# BPF_LNA_1550A.net
KiCad netlist of a schematic drawn in EAGLE
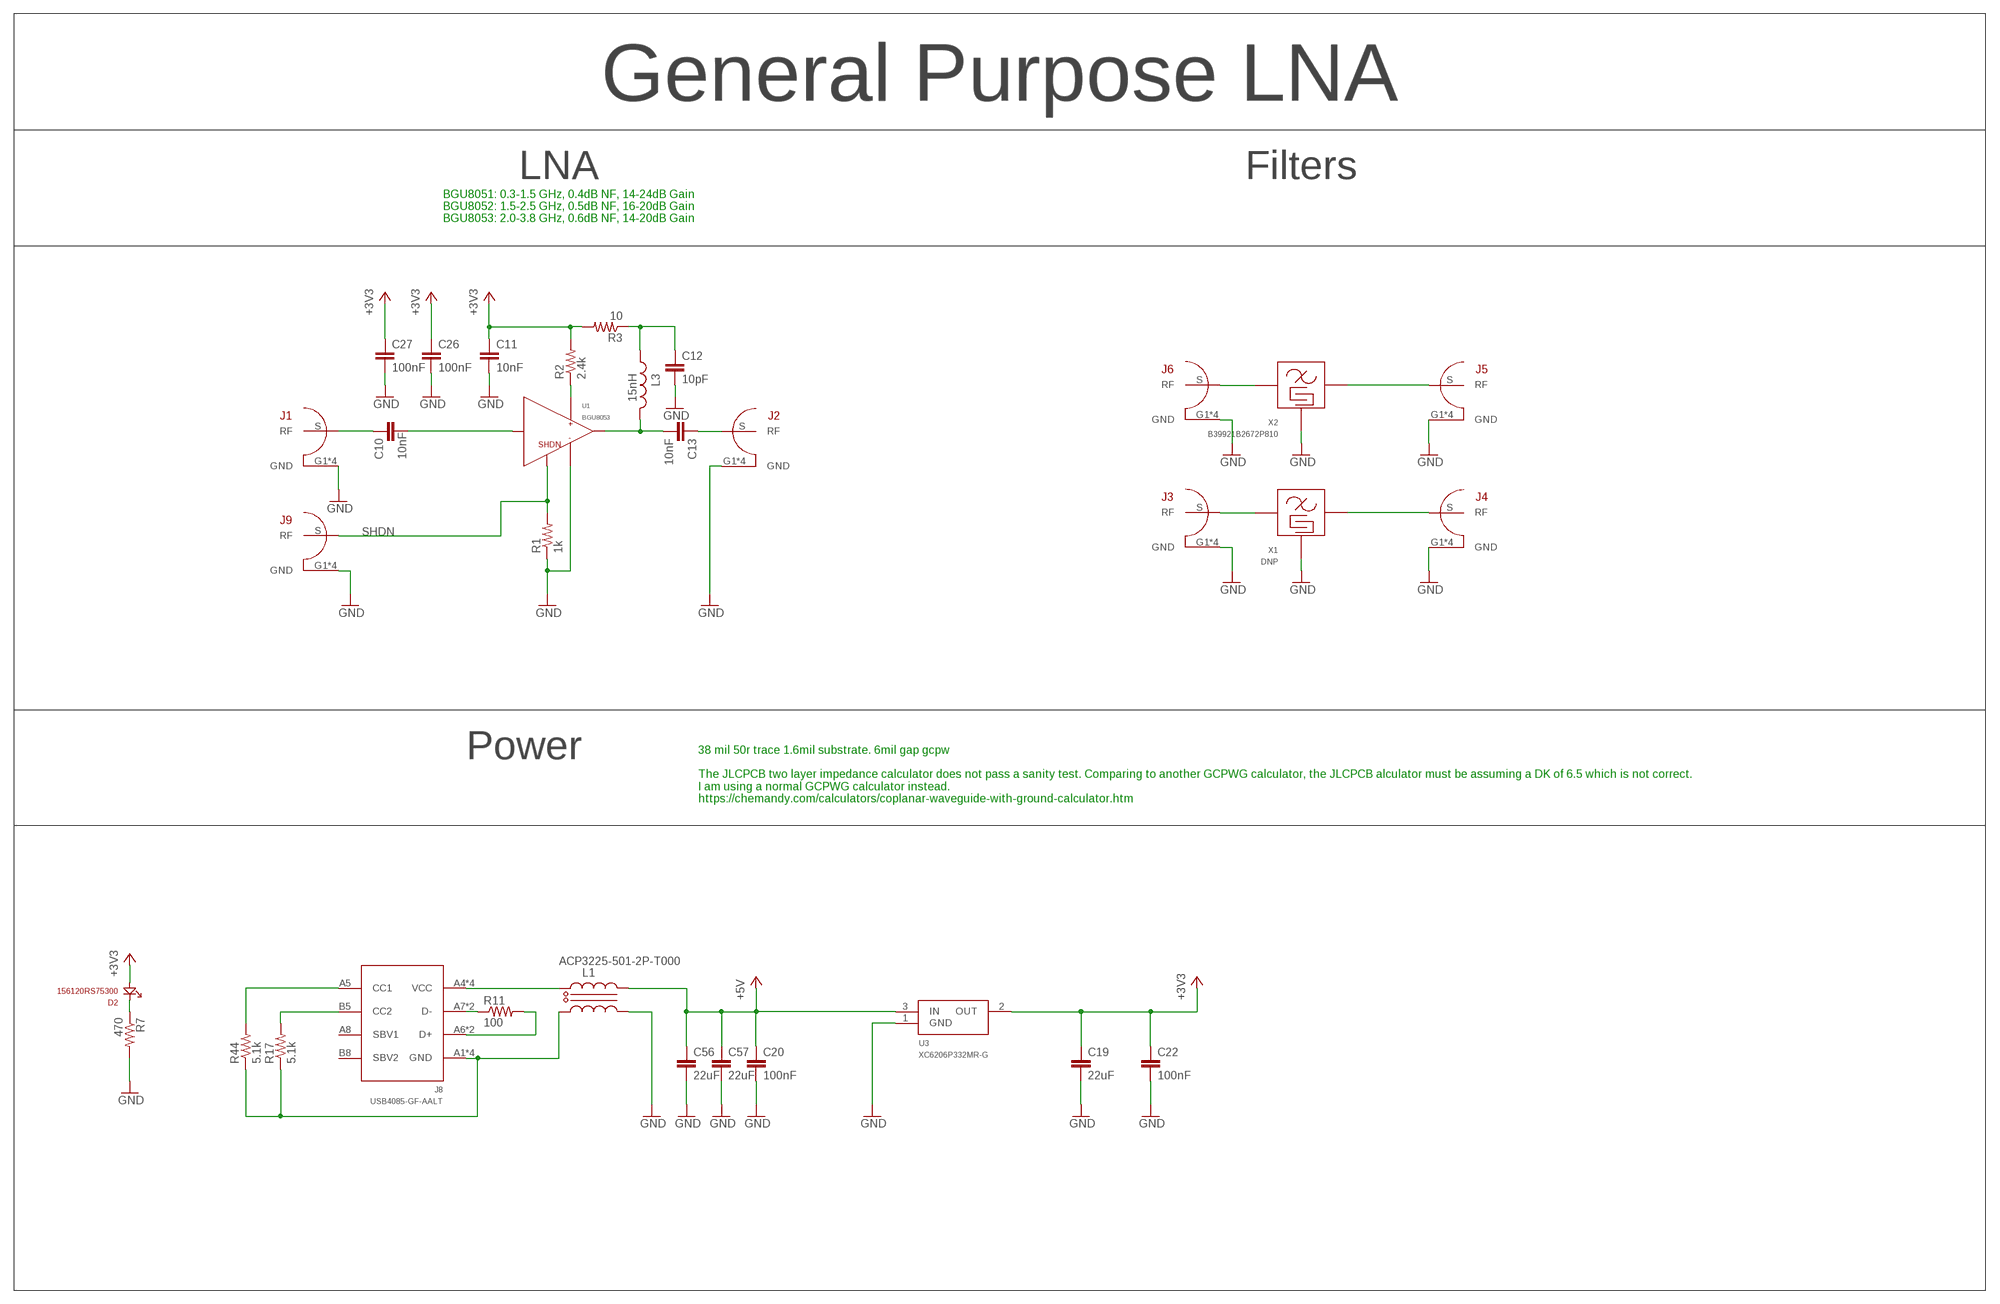
[diagram p0: schematic, sheet 1]

(export (version "E")
  (design (tool "Eeschema 10.0.6"))
  (components
    (comp (ref "C10")
      (value "10nF")
      (footprint "eagle-import:0603")
      (libsource (lib "eagle-import") (part "0603_CAPACITOR"))
    )
    (comp (ref "C11")
      (value "10nF")
      (footprint "eagle-import:0603")
      (libsource (lib "eagle-import") (part "0603_CAPACITOR"))
    )
    (comp (ref "C12")
      (value "10pF")
      (footprint "eagle-import:0603")
      (libsource (lib "eagle-import") (part "0603_CAPACITOR"))
    )
    (comp (ref "C13")
      (value "10nF")
      (footprint "eagle-import:0603")
      (libsource (lib "eagle-import") (part "0603_CAPACITOR"))
    )
    (comp (ref "C19")
      (value "22uF")
      (footprint "eagle-import:C1206")
      (libsource (lib "eagle-import") (part "C-EUC1206"))
    )
    (comp (ref "C20")
      (value "100nF")
      (footprint "eagle-import:0603")
      (libsource (lib "eagle-import") (part "0603_CAPACITOR"))
    )
    (comp (ref "C22")
      (value "100nF")
      (footprint "eagle-import:0603")
      (libsource (lib "eagle-import") (part "0603_CAPACITOR"))
    )
    (comp (ref "C26")
      (value "100nF")
      (footprint "eagle-import:0603")
      (libsource (lib "eagle-import") (part "0603_CAPACITOR"))
    )
    (comp (ref "C27")
      (value "100nF")
      (footprint "eagle-import:0603")
      (libsource (lib "eagle-import") (part "0603_CAPACITOR"))
    )
    (comp (ref "C56")
      (value "22uF")
      (footprint "eagle-import:C1206")
      (libsource (lib "eagle-import") (part "C-EUC1206"))
    )
    (comp (ref "C57")
      (value "22uF")
      (footprint "eagle-import:C1206")
      (libsource (lib "eagle-import") (part "C-EUC1206"))
    )
    (comp (ref "D2")
      (value "156120RS75300")
      (footprint "eagle-import:1206_REV")
      (fields (field (name "PARTNO") "732-5031-1-ND"))
      (libsource (lib "eagle-import") (part "156120RS75300"))
    )
    (comp (ref "J1")
      (value "0733910070")
      (footprint "eagle-import:CONREVSMA008-G")
      (fields (field (name "PARTNO") "WM5544-ND"))
      (libsource (lib "eagle-import") (part "0733910070"))
    )
    (comp (ref "J2")
      (value "0733910070")
      (footprint "eagle-import:CONREVSMA008-G")
      (fields (field (name "PARTNO") "WM5544-ND"))
      (libsource (lib "eagle-import") (part "0733910070"))
    )
    (comp (ref "J3")
      (value "0733910070")
      (footprint "eagle-import:CONREVSMA008-G")
      (fields (field (name "PARTNO") "WM5544-ND"))
      (libsource (lib "eagle-import") (part "0733910070"))
    )
    (comp (ref "J4")
      (value "0733910070")
      (footprint "eagle-import:CONREVSMA008-G")
      (fields (field (name "PARTNO") "WM5544-ND"))
      (libsource (lib "eagle-import") (part "0733910070"))
    )
    (comp (ref "J5")
      (value "0733910070")
      (footprint "eagle-import:CONREVSMA008-G")
      (fields (field (name "PARTNO") "WM5544-ND"))
      (libsource (lib "eagle-import") (part "0733910070"))
    )
    (comp (ref "J6")
      (value "0733910070")
      (footprint "eagle-import:CONREVSMA008-G")
      (fields (field (name "PARTNO") "WM5544-ND"))
      (libsource (lib "eagle-import") (part "0733910070"))
    )
    (comp (ref "J8")
      (value "USB4085-GF-AALT")
      (footprint "eagle-import:USBC2")
      (libsource (lib "eagle-import") (part "USB4085-GF-AALT"))
    )
    (comp (ref "J9")
      (value "0733910070")
      (footprint "eagle-import:CONREVSMA008-G")
      (fields (field (name "PARTNO") "WM5544-ND"))
      (libsource (lib "eagle-import") (part "0733910070"))
    )
    (comp (ref "L1")
      (value "ACP3225-501-2P-T000")
      (footprint "eagle-import:3225")
      (fields (field (name "PARTNO") "445-172408-1-ND"))
      (libsource (lib "eagle-import") (part "ACP3225-501-2P-T000"))
    )
    (comp (ref "L3")
      (value "15nH")
      (footprint "eagle-import:0603")
      (libsource (lib "eagle-import") (part "0603_INDUCTOR"))
    )
    (comp (ref "R1")
      (value "1k")
      (footprint "eagle-import:0603")
      (libsource (lib "eagle-import") (part "0603_RESISTOR"))
    )
    (comp (ref "R2")
      (value "2.4k")
      (footprint "eagle-import:0603")
      (libsource (lib "eagle-import") (part "0603_RESISTOR"))
    )
    (comp (ref "R3")
      (value "10")
      (footprint "eagle-import:0603")
      (libsource (lib "eagle-import") (part "0603_RESISTOR"))
    )
    (comp (ref "R7")
      (value "470")
      (footprint "eagle-import:0603")
      (libsource (lib "eagle-import") (part "0603_RESISTOR"))
    )
    (comp (ref "R11")
      (value "100")
      (footprint "eagle-import:0603")
      (libsource (lib "eagle-import") (part "0603_RESISTOR"))
    )
    (comp (ref "R17")
      (value "5.1k")
      (footprint "eagle-import:0603")
      (libsource (lib "eagle-import") (part "0603_RESISTOR"))
    )
    (comp (ref "R44")
      (value "5.1k")
      (footprint "eagle-import:0603")
      (libsource (lib "eagle-import") (part "0603_RESISTOR"))
    )
    (comp (ref "U1")
      (value "BGU8053")
      (footprint "eagle-import:SOT1327-1")
      (fields (field (name "PARTNO") "568-BGU8051XCT-ND"))
      (libsource (lib "eagle-import") (part "BGU8051"))
    )
    (comp (ref "U3")
      (value "XC6206P332MR-G")
      (footprint "eagle-import:SOT23-3_CENTERED")
      (libsource (lib "eagle-import") (part "XC6206P332MR-G"))
    )
    (comp (ref "X1")
      (value "DNP")
      (footprint "eagle-import:TA0862A")
      (fields (field (name "PARTNO") "4606-TA0862ACT-ND"))
      (libsource (lib "eagle-import") (part "TA0862A"))
    )
    (comp (ref "X2")
      (value "B39921B2672P810")
      (footprint "eagle-import:B2672")
      (fields (field (name "PARTNO") "1752-B39921B2672P810CT-ND"))
      (libsource (lib "eagle-import") (part "B39921B2672P810"))
    )
  )
  (nets
    (net (code "1") (name "+3V3") (class "Default")
      (node (ref "C11") (pin "1") (pinfunction "1_1") (pintype "passive"))
      (node (ref "C19") (pin "1") (pinfunction "1_1") (pintype "passive"))
      (node (ref "C22") (pin "1") (pinfunction "1_1") (pintype "passive"))
      (node (ref "C26") (pin "1") (pinfunction "1_1") (pintype "passive"))
      (node (ref "C27") (pin "1") (pinfunction "1_1") (pintype "passive"))
      (node (ref "D2") (pin "A") (pinfunction "A_A") (pintype "bidirectional"))
      (node (ref "R2") (pin "2") (pinfunction "2_2") (pintype "passive"))
      (node (ref "R3") (pin "2") (pinfunction "2_2") (pintype "passive"))
      (node (ref "U3") (pin "2") (pinfunction "OUT_2") (pintype "bidirectional"))
    )
    (net (code "2") (name "+5V") (class "Default")
      (node (ref "C20") (pin "1") (pinfunction "1_1") (pintype "passive"))
      (node (ref "C56") (pin "1") (pinfunction "1_1") (pintype "passive"))
      (node (ref "C57") (pin "1") (pinfunction "1_1") (pintype "passive"))
      (node (ref "L1") (pin "4") (pinfunction "1OUT_4") (pintype "bidirectional"))
      (node (ref "U3") (pin "3") (pinfunction "IN_3") (pintype "bidirectional"))
    )
    (net (code "3") (name "/SHDN") (class "Default")
      (node (ref "J9") (pin "S") (pinfunction "RF_S") (pintype "bidirectional"))
      (node (ref "R1") (pin "2") (pinfunction "2_2") (pintype "passive"))
      (node (ref "U1") (pin "6") (pinfunction "SHDN_6") (pintype "bidirectional"))
    )
    (net (code "4") (name "GND") (class "Default")
      (node (ref "C11") (pin "2") (pinfunction "2_2") (pintype "passive"))
      (node (ref "C12") (pin "2") (pinfunction "2_2") (pintype "passive"))
      (node (ref "C19") (pin "2") (pinfunction "2_2") (pintype "passive"))
      (node (ref "C20") (pin "2") (pinfunction "2_2") (pintype "passive"))
      (node (ref "C22") (pin "2") (pinfunction "2_2") (pintype "passive"))
      (node (ref "C26") (pin "2") (pinfunction "2_2") (pintype "passive"))
      (node (ref "C27") (pin "2") (pinfunction "2_2") (pintype "passive"))
      (node (ref "C56") (pin "2") (pinfunction "2_2") (pintype "passive"))
      (node (ref "C57") (pin "2") (pinfunction "2_2") (pintype "passive"))
      (node (ref "J1") (pin "G1") (pinfunction "GND_G1") (pintype "bidirectional"))
      (node (ref "J1") (pin "G2") (pinfunction "GND_G2") (pintype "bidirectional"))
      (node (ref "J1") (pin "G3") (pinfunction "GND_G3") (pintype "bidirectional"))
      (node (ref "J1") (pin "G4") (pinfunction "GND_G4") (pintype "bidirectional"))
      (node (ref "J2") (pin "G1") (pinfunction "GND_G1") (pintype "bidirectional"))
      (node (ref "J2") (pin "G2") (pinfunction "GND_G2") (pintype "bidirectional"))
      (node (ref "J2") (pin "G3") (pinfunction "GND_G3") (pintype "bidirectional"))
      (node (ref "J2") (pin "G4") (pinfunction "GND_G4") (pintype "bidirectional"))
      (node (ref "J3") (pin "G1") (pinfunction "GND_G1") (pintype "bidirectional"))
      (node (ref "J3") (pin "G2") (pinfunction "GND_G2") (pintype "bidirectional"))
      (node (ref "J3") (pin "G3") (pinfunction "GND_G3") (pintype "bidirectional"))
      (node (ref "J3") (pin "G4") (pinfunction "GND_G4") (pintype "bidirectional"))
      (node (ref "J4") (pin "G1") (pinfunction "GND_G1") (pintype "bidirectional"))
      (node (ref "J4") (pin "G2") (pinfunction "GND_G2") (pintype "bidirectional"))
      (node (ref "J4") (pin "G3") (pinfunction "GND_G3") (pintype "bidirectional"))
      (node (ref "J4") (pin "G4") (pinfunction "GND_G4") (pintype "bidirectional"))
      (node (ref "J5") (pin "G1") (pinfunction "GND_G1") (pintype "bidirectional"))
      (node (ref "J5") (pin "G2") (pinfunction "GND_G2") (pintype "bidirectional"))
      (node (ref "J5") (pin "G3") (pinfunction "GND_G3") (pintype "bidirectional"))
      (node (ref "J5") (pin "G4") (pinfunction "GND_G4") (pintype "bidirectional"))
      (node (ref "J6") (pin "G1") (pinfunction "GND_G1") (pintype "bidirectional"))
      (node (ref "J6") (pin "G2") (pinfunction "GND_G2") (pintype "bidirectional"))
      (node (ref "J6") (pin "G3") (pinfunction "GND_G3") (pintype "bidirectional"))
      (node (ref "J6") (pin "G4") (pinfunction "GND_G4") (pintype "bidirectional"))
      (node (ref "J9") (pin "G1") (pinfunction "GND_G1") (pintype "bidirectional"))
      (node (ref "J9") (pin "G2") (pinfunction "GND_G2") (pintype "bidirectional"))
      (node (ref "J9") (pin "G3") (pinfunction "GND_G3") (pintype "bidirectional"))
      (node (ref "J9") (pin "G4") (pinfunction "GND_G4") (pintype "bidirectional"))
      (node (ref "L1") (pin "3") (pinfunction "2OUT_3") (pintype "bidirectional"))
      (node (ref "R1") (pin "1") (pinfunction "1_1") (pintype "passive"))
      (node (ref "R7") (pin "2") (pinfunction "2_2") (pintype "passive"))
      (node (ref "U1") (pin "EP") (pinfunction "GND_EP") (pintype "bidirectional"))
      (node (ref "U3") (pin "1") (pinfunction "GND_1") (pintype "bidirectional"))
      (node (ref "X1") (pin "A") (pinfunction "GND_A") (pintype "bidirectional"))
      (node (ref "X1") (pin "C") (pinfunction "GND_C") (pintype "bidirectional"))
      (node (ref "X1") (pin "D") (pinfunction "GND_D") (pintype "bidirectional"))
      (node (ref "X1") (pin "F") (pinfunction "GND_F") (pintype "bidirectional"))
      (node (ref "X2") (pin "2") (pinfunction "GND_2") (pintype "bidirectional"))
      (node (ref "X2") (pin "3") (pinfunction "GND_3") (pintype "bidirectional"))
      (node (ref "X2") (pin "5") (pinfunction "GND_5") (pintype "bidirectional"))
    )
    (net (code "5") (name "Net-(D2-PadK)") (class "Default")
      (node (ref "D2") (pin "K") (pinfunction "K_K") (pintype "bidirectional"))
      (node (ref "R7") (pin "1") (pinfunction "1_1") (pintype "passive"))
    )
    (net (code "6") (name "Net-(J1-RF)") (class "Default")
      (node (ref "C10") (pin "1") (pinfunction "1_1") (pintype "passive"))
      (node (ref "J1") (pin "S") (pinfunction "RF_S") (pintype "bidirectional"))
    )
    (net (code "7") (name "Net-(J2-RF)") (class "Default")
      (node (ref "C13") (pin "1") (pinfunction "1_1") (pintype "passive"))
      (node (ref "J2") (pin "S") (pinfunction "RF_S") (pintype "bidirectional"))
    )
    (net (code "8") (name "Net-(J3-RF)") (class "Default")
      (node (ref "J3") (pin "S") (pinfunction "RF_S") (pintype "bidirectional"))
      (node (ref "X1") (pin "B") (pinfunction "P$1_B") (pintype "bidirectional"))
    )
    (net (code "9") (name "Net-(J4-RF)") (class "Default")
      (node (ref "J4") (pin "S") (pinfunction "RF_S") (pintype "bidirectional"))
      (node (ref "X1") (pin "E") (pinfunction "P$2_E") (pintype "bidirectional"))
    )
    (net (code "10") (name "Net-(J5-RF)") (class "Default")
      (node (ref "J5") (pin "S") (pinfunction "RF_S") (pintype "bidirectional"))
      (node (ref "X2") (pin "4") (pinfunction "P$2_4") (pintype "bidirectional"))
    )
    (net (code "11") (name "Net-(J6-RF)") (class "Default")
      (node (ref "J6") (pin "S") (pinfunction "RF_S") (pintype "bidirectional"))
      (node (ref "X2") (pin "1") (pinfunction "P$1_1") (pintype "bidirectional"))
    )
    (net (code "12") (name "Net-(J8-CC1)") (class "Default")
      (node (ref "J8") (pin "A5") (pinfunction "CC1_A5") (pintype "bidirectional"))
      (node (ref "R44") (pin "2") (pinfunction "2_2") (pintype "passive"))
    )
    (net (code "13") (name "Net-(J8-CC2)") (class "Default")
      (node (ref "J8") (pin "B5") (pinfunction "CC2_B5") (pintype "bidirectional"))
      (node (ref "R17") (pin "2") (pinfunction "2_2") (pintype "passive"))
    )
    (net (code "14") (name "Net-(J8-D+-PadA6)") (class "Default")
      (node (ref "J8") (pin "A6") (pinfunction "D+_A6") (pintype "bidirectional"))
      (node (ref "J8") (pin "B6") (pinfunction "D+_B6") (pintype "bidirectional"))
      (node (ref "R11") (pin "2") (pinfunction "2_2") (pintype "passive"))
    )
    (net (code "15") (name "Net-(J8-D--PadA7)") (class "Default")
      (node (ref "J8") (pin "A7") (pinfunction "D-_A7") (pintype "bidirectional"))
      (node (ref "J8") (pin "B7") (pinfunction "D-_B7") (pintype "bidirectional"))
      (node (ref "R11") (pin "1") (pinfunction "1_1") (pintype "passive"))
    )
    (net (code "16") (name "Net-(L1-1IN)") (class "Default")
      (node (ref "J8") (pin "A4") (pinfunction "VCC_A4") (pintype "bidirectional"))
      (node (ref "J8") (pin "A9") (pinfunction "VCC_A9") (pintype "bidirectional"))
      (node (ref "J8") (pin "B4") (pinfunction "VCC_B4") (pintype "bidirectional"))
      (node (ref "J8") (pin "B9") (pinfunction "VCC_B9") (pintype "bidirectional"))
      (node (ref "L1") (pin "1") (pinfunction "1IN_1") (pintype "bidirectional"))
    )
    (net (code "17") (name "Net-(L1-2IN)") (class "Default")
      (node (ref "J8") (pin "A1") (pinfunction "GND_A1") (pintype "bidirectional"))
      (node (ref "J8") (pin "A12") (pinfunction "GND_A12") (pintype "bidirectional"))
      (node (ref "J8") (pin "B1") (pinfunction "GND_B1") (pintype "bidirectional"))
      (node (ref "J8") (pin "B12") (pinfunction "GND_B12") (pintype "bidirectional"))
      (node (ref "L1") (pin "2") (pinfunction "2IN_2") (pintype "bidirectional"))
      (node (ref "R17") (pin "1") (pinfunction "1_1") (pintype "passive"))
      (node (ref "R44") (pin "1") (pinfunction "1_1") (pintype "passive"))
    )
    (net (code "18") (name "Net-(L3-P$1)") (class "Default")
      (node (ref "C12") (pin "1") (pinfunction "1_1") (pintype "passive"))
      (node (ref "L3") (pin "1") (pinfunction "P$1_1") (pintype "bidirectional"))
      (node (ref "R3") (pin "1") (pinfunction "1_1") (pintype "passive"))
    )
    (net (code "19") (name "Net-(L3-P$2)") (class "Default")
      (node (ref "C13") (pin "2") (pinfunction "2_2") (pintype "passive"))
      (node (ref "L3") (pin "2") (pinfunction "P$2_2") (pintype "bidirectional"))
      (node (ref "U1") (pin "7") (pinfunction "OUT_7") (pintype "bidirectional"))
    )
    (net (code "20") (name "Net-(U1-IN)") (class "Default")
      (node (ref "C10") (pin "2") (pinfunction "2_2") (pintype "passive"))
      (node (ref "U1") (pin "2") (pinfunction "IN_2") (pintype "bidirectional"))
    )
    (net (code "21") (name "Net-(U1-VCC)") (class "Default")
      (node (ref "R2") (pin "1") (pinfunction "1_1") (pintype "passive"))
      (node (ref "U1") (pin "1") (pinfunction "VCC_1") (pintype "bidirectional"))
    )
    (net (code "22") (name "unconnected-(J8-SBV1-PadA8)") (class "Default")
      (node (ref "J8") (pin "A8") (pinfunction "SBV1_A8") (pintype "bidirectional"))
    )
    (net (code "23") (name "unconnected-(J8-SBV2-PadB8)") (class "Default")
      (node (ref "J8") (pin "B8") (pinfunction "SBV2_B8") (pintype "bidirectional"))
    )
  )
)
